# garden_circ.net
KiCad netlist of a schematic drawn in EAGLE
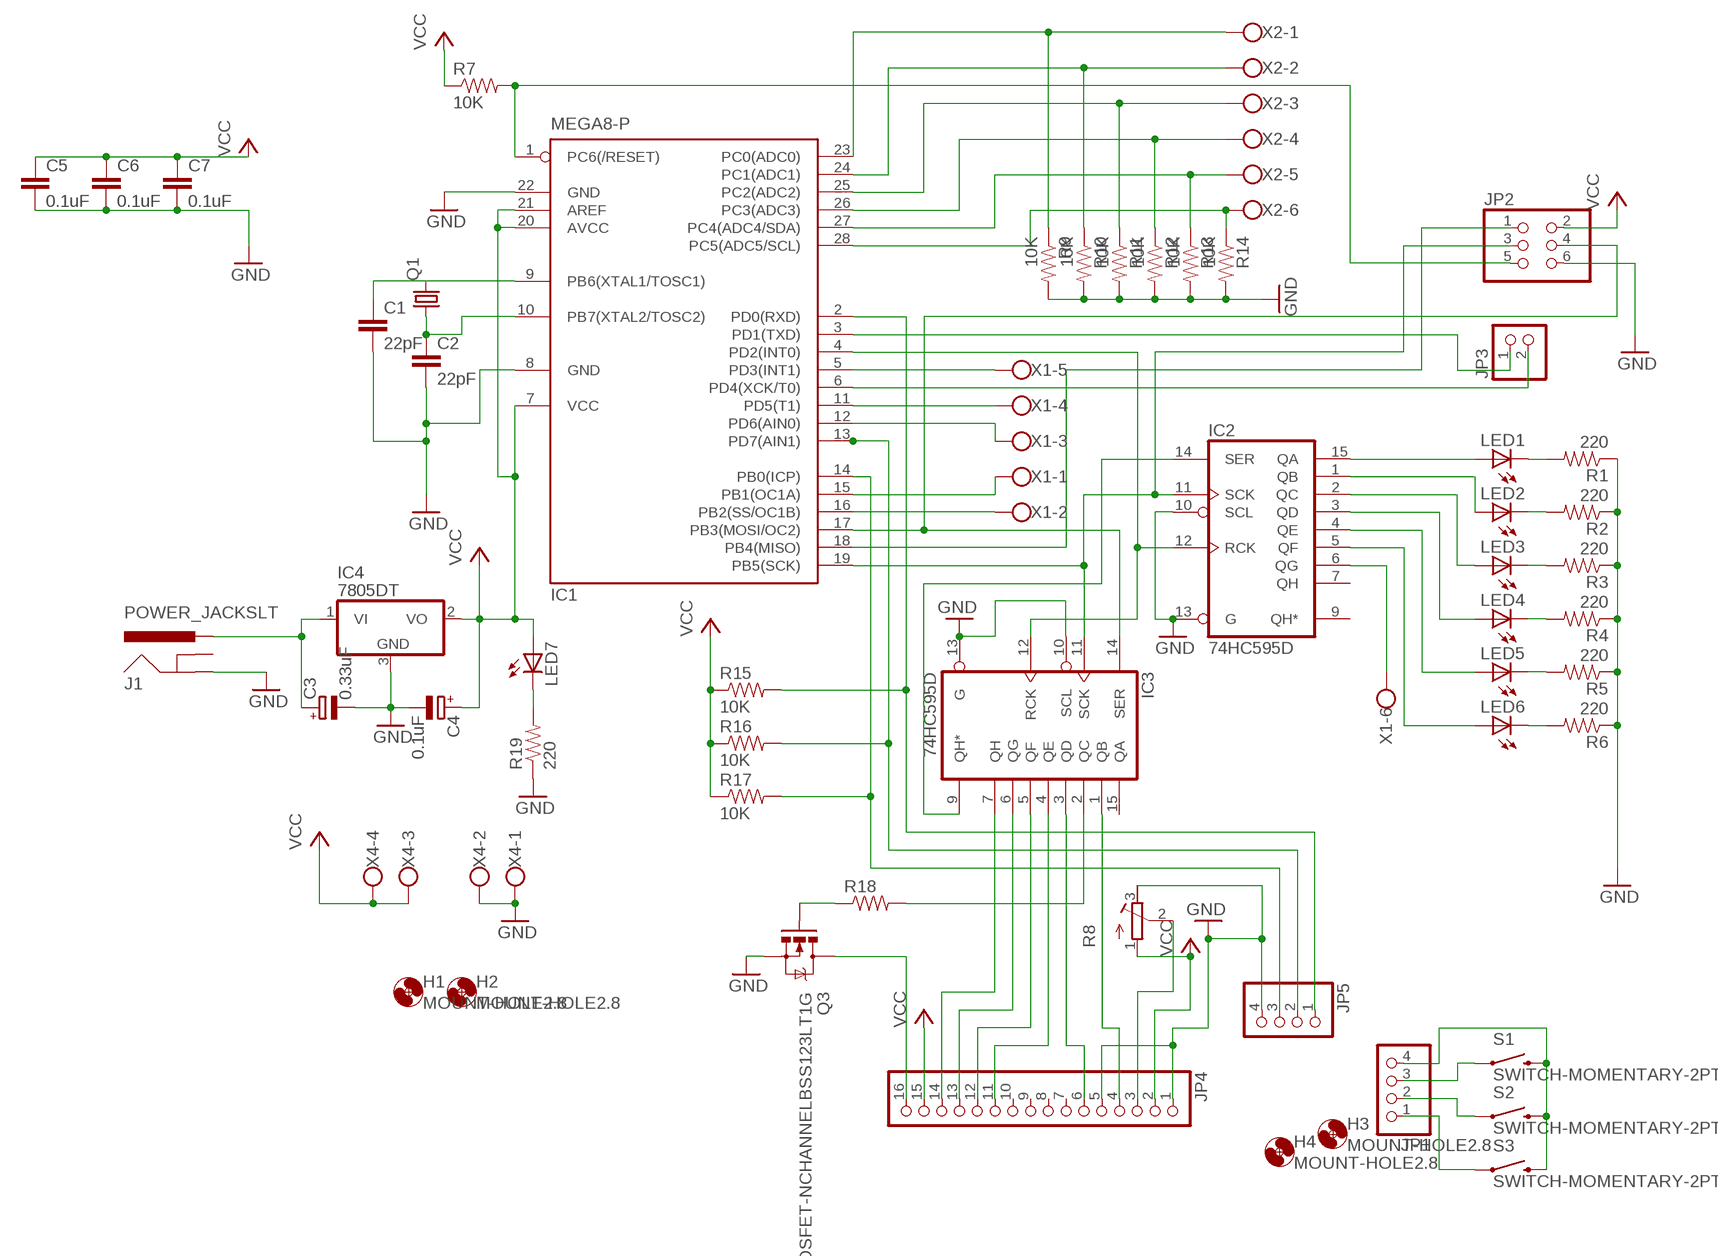
[diagram p0: schematic, sheet 1]

(export (version "E")
  (design (tool "Eeschema 10.0.6"))
  (components
    (comp (ref "C1")
      (value "22pF")
      (footprint "eagle-import:0805")
      (libsource (lib "eagle-import") (part "CAP0805"))
    )
    (comp (ref "C2")
      (value "22pF")
      (footprint "eagle-import:0805")
      (libsource (lib "eagle-import") (part "CAP0805"))
    )
    (comp (ref "C3")
      (value "0.33uF")
      (footprint "eagle-import:SMC_C")
      (libsource (lib "eagle-import") (part "CPOL-EUSMCC"))
    )
    (comp (ref "C4")
      (value "0.1uF")
      (footprint "eagle-import:SMC_C")
      (libsource (lib "eagle-import") (part "CPOL-EUSMCC"))
    )
    (comp (ref "C5")
      (value "0.1uF")
      (footprint "eagle-import:0805")
      (libsource (lib "eagle-import") (part "CAP0805"))
    )
    (comp (ref "C6")
      (value "0.1uF")
      (footprint "eagle-import:0805")
      (libsource (lib "eagle-import") (part "CAP0805"))
    )
    (comp (ref "C7")
      (value "0.1uF")
      (footprint "eagle-import:0805")
      (libsource (lib "eagle-import") (part "CAP0805"))
    )
    (comp (ref "H1")
      (value "MOUNT-HOLE2.8")
      (footprint "eagle-import:2,8")
      (libsource (lib "eagle-import") (part "MOUNT-HOLE2.8"))
    )
    (comp (ref "H2")
      (value "MOUNT-HOLE2.8")
      (footprint "eagle-import:2,8")
      (libsource (lib "eagle-import") (part "MOUNT-HOLE2.8"))
    )
    (comp (ref "H3")
      (value "MOUNT-HOLE2.8")
      (footprint "eagle-import:2,8")
      (libsource (lib "eagle-import") (part "MOUNT-HOLE2.8"))
    )
    (comp (ref "H4")
      (value "MOUNT-HOLE2.8")
      (footprint "eagle-import:2,8")
      (libsource (lib "eagle-import") (part "MOUNT-HOLE2.8"))
    )
    (comp (ref "IC1")
      (value "MEGA8-P")
      (footprint "eagle-import:DIL28-3")
      (libsource (lib "eagle-import") (part "MEGA8-P"))
    )
    (comp (ref "IC2")
      (value "74HC595D")
      (footprint "eagle-import:SO16")
      (libsource (lib "eagle-import") (part "74595DHC"))
    )
    (comp (ref "IC3")
      (value "74HC595D")
      (footprint "eagle-import:SO16")
      (libsource (lib "eagle-import") (part "74595DHC"))
    )
    (comp (ref "IC4")
      (value "7805DT")
      (footprint "eagle-import:TO252")
      (libsource (lib "eagle-import") (part "78DT05"))
    )
    (comp (ref "J1")
      (value "POWER_JACKSLT")
      (footprint "eagle-import:POWER_JACK_SLOT")
      (libsource (lib "eagle-import") (part "POWER_JACKSLT"))
    )
    (comp (ref "JP1")
      (value "PINHD-1X4")
      (footprint "eagle-import:1X04")
      (libsource (lib "eagle-import") (part "PINHD-1X4"))
    )
    (comp (ref "JP2")
      (value "PINHD-2X3")
      (footprint "eagle-import:2X03")
      (libsource (lib "eagle-import") (part "PINHD-2X3"))
    )
    (comp (ref "JP3")
      (value "PINHD-1X2")
      (footprint "eagle-import:1X02")
      (libsource (lib "eagle-import") (part "PINHD-1X2"))
    )
    (comp (ref "JP4")
      (value "PINHD-1X16")
      (footprint "eagle-import:1X16")
      (libsource (lib "eagle-import") (part "PINHD-1X16"))
    )
    (comp (ref "JP5")
      (value "PINHD-1X4")
      (footprint "eagle-import:1X04")
      (libsource (lib "eagle-import") (part "PINHD-1X4"))
    )
    (comp (ref "LED1")
      (value "LED3MM")
      (footprint "eagle-import:LED3MM")
      (libsource (lib "eagle-import") (part "LED3MM"))
    )
    (comp (ref "LED2")
      (value "LED3MM")
      (footprint "eagle-import:LED3MM")
      (libsource (lib "eagle-import") (part "LED3MM"))
    )
    (comp (ref "LED3")
      (value "LED3MM")
      (footprint "eagle-import:LED3MM")
      (libsource (lib "eagle-import") (part "LED3MM"))
    )
    (comp (ref "LED4")
      (value "LED3MM")
      (footprint "eagle-import:LED3MM")
      (libsource (lib "eagle-import") (part "LED3MM"))
    )
    (comp (ref "LED5")
      (value "LED3MM")
      (footprint "eagle-import:LED3MM")
      (libsource (lib "eagle-import") (part "LED3MM"))
    )
    (comp (ref "LED6")
      (value "LED3MM")
      (footprint "eagle-import:LED3MM")
      (libsource (lib "eagle-import") (part "LED3MM"))
    )
    (comp (ref "LED7")
      (value "LEDSML0805")
      (footprint "eagle-import:SML0805")
      (libsource (lib "eagle-import") (part "LEDSML0805"))
    )
    (comp (ref "Q1")
      (value "CRYSTALHC49UP")
      (footprint "eagle-import:HC49UP")
      (libsource (lib "eagle-import") (part "CRYSTALHC49UP"))
    )
    (comp (ref "Q3")
      (value "MOSFET-NCHANNELBSS123LT1G")
      (footprint "eagle-import:SOT23")
      (libsource (lib "eagle-import") (part "MOSFET-NCHANNELBSS123LT1G"))
    )
    (comp (ref "R1")
      (value "220")
      (footprint "eagle-import:0805")
      (libsource (lib "eagle-import") (part "RESISTOR0805-RES"))
    )
    (comp (ref "R2")
      (value "220")
      (footprint "eagle-import:0805")
      (libsource (lib "eagle-import") (part "RESISTOR0805-RES"))
    )
    (comp (ref "R3")
      (value "220")
      (footprint "eagle-import:0805")
      (libsource (lib "eagle-import") (part "RESISTOR0805-RES"))
    )
    (comp (ref "R4")
      (value "220")
      (footprint "eagle-import:0805")
      (libsource (lib "eagle-import") (part "RESISTOR0805-RES"))
    )
    (comp (ref "R5")
      (value "220")
      (footprint "eagle-import:0805")
      (libsource (lib "eagle-import") (part "RESISTOR0805-RES"))
    )
    (comp (ref "R6")
      (value "220")
      (footprint "eagle-import:0805")
      (libsource (lib "eagle-import") (part "RESISTOR0805-RES"))
    )
    (comp (ref "R7")
      (value "10K")
      (footprint "eagle-import:0805")
      (libsource (lib "eagle-import") (part "RESISTOR0805-RES"))
    )
    (comp (ref "R8")
      (value "R-TRIMM3202")
      (footprint "eagle-import:RTRIM3202")
      (libsource (lib "eagle-import") (part "R-TRIMM3202"))
    )
    (comp (ref "R9")
      (value "10K")
      (footprint "eagle-import:0805")
      (libsource (lib "eagle-import") (part "RESISTOR0805-RES"))
    )
    (comp (ref "R10")
      (value "10K")
      (footprint "eagle-import:0805")
      (libsource (lib "eagle-import") (part "RESISTOR0805-RES"))
    )
    (comp (ref "R11")
      (value "10K")
      (footprint "eagle-import:0805")
      (libsource (lib "eagle-import") (part "RESISTOR0805-RES"))
    )
    (comp (ref "R12")
      (value "10K")
      (footprint "eagle-import:0805")
      (libsource (lib "eagle-import") (part "RESISTOR0805-RES"))
    )
    (comp (ref "R13")
      (value "10K")
      (footprint "eagle-import:0805")
      (libsource (lib "eagle-import") (part "RESISTOR0805-RES"))
    )
    (comp (ref "R14")
      (value "10K")
      (footprint "eagle-import:0805")
      (libsource (lib "eagle-import") (part "RESISTOR0805-RES"))
    )
    (comp (ref "R15")
      (value "10K")
      (footprint "eagle-import:0805")
      (libsource (lib "eagle-import") (part "RESISTOR0805-RES"))
    )
    (comp (ref "R16")
      (value "10K")
      (footprint "eagle-import:0805")
      (libsource (lib "eagle-import") (part "RESISTOR0805-RES"))
    )
    (comp (ref "R17")
      (value "10K")
      (footprint "eagle-import:0805")
      (libsource (lib "eagle-import") (part "RESISTOR0805-RES"))
    )
    (comp (ref "R18")
      (value "RESISTOR0805-RES")
      (footprint "eagle-import:0805")
      (libsource (lib "eagle-import") (part "RESISTOR0805-RES"))
    )
    (comp (ref "R19")
      (value "220")
      (footprint "eagle-import:0805")
      (libsource (lib "eagle-import") (part "RESISTOR0805-RES"))
    )
    (comp (ref "S1")
      (value "SWITCH-MOMENTARY-2PTH")
      (footprint "eagle-import:TACTILE-PTH")
      (libsource (lib "eagle-import") (part "SWITCH-MOMENTARY-2PTH"))
    )
    (comp (ref "S2")
      (value "SWITCH-MOMENTARY-2PTH")
      (footprint "eagle-import:TACTILE-PTH")
      (libsource (lib "eagle-import") (part "SWITCH-MOMENTARY-2PTH"))
    )
    (comp (ref "S3")
      (value "SWITCH-MOMENTARY-2PTH")
      (footprint "eagle-import:TACTILE-PTH")
      (libsource (lib "eagle-import") (part "SWITCH-MOMENTARY-2PTH"))
    )
    (comp (ref "X1")
      (value "W237-136")
      (footprint "eagle-import:W237-136")
      (fields (field (name "MPN") "237-136"))
      (libsource (lib "eagle-import") (part "W237-136"))
    )
    (comp (ref "X2")
      (value "W237-136")
      (footprint "eagle-import:W237-136")
      (fields (field (name "MPN") "237-136"))
      (libsource (lib "eagle-import") (part "W237-136"))
    )
    (comp (ref "X4")
      (value "W237-4")
      (footprint "eagle-import:W237-4")
      (libsource (lib "eagle-import") (part "W237-4"))
    )
  )
  (nets
    (net (code "1") (name "GND") (class "Default")
      (node (ref "C1") (pin "2") (pinfunction "2_2") (pintype "passive"))
      (node (ref "C2") (pin "2") (pinfunction "2_2") (pintype "passive"))
      (node (ref "C3") (pin "-") (pinfunction "-_-") (pintype "passive"))
      (node (ref "C4") (pin "-") (pinfunction "-_-") (pintype "passive"))
      (node (ref "C5") (pin "2") (pinfunction "2_2") (pintype "passive"))
      (node (ref "C6") (pin "2") (pinfunction "2_2") (pintype "passive"))
      (node (ref "C7") (pin "2") (pinfunction "2_2") (pintype "passive"))
      (node (ref "IC1") (pin "22") (pinfunction "GND_22") (pintype "power_in"))
      (node (ref "IC1") (pin "8") (pinfunction "GND_8") (pintype "power_in"))
      (node (ref "IC2") (pin "10") (pinfunction "SCL_10") (pintype "input"))
      (node (ref "IC2") (pin "13") (pinfunction "G_13") (pintype "input"))
      (node (ref "IC3") (pin "10") (pinfunction "SCL_10") (pintype "input"))
      (node (ref "IC3") (pin "13") (pinfunction "G_13") (pintype "input"))
      (node (ref "IC4") (pin "3") (pinfunction "GND_3") (pintype "passive"))
      (node (ref "J1") (pin "GND@2") (pinfunction "GND_GND@2") (pintype "bidirectional"))
      (node (ref "JP2") (pin "6") (pinfunction "6_6") (pintype "passive"))
      (node (ref "JP4") (pin "1") (pinfunction "1_1") (pintype "passive"))
      (node (ref "JP4") (pin "5") (pinfunction "5_5") (pintype "passive"))
      (node (ref "JP5") (pin "4") (pinfunction "4_4") (pintype "passive"))
      (node (ref "Q3") (pin "2") (pinfunction "S_2") (pintype "passive"))
      (node (ref "R1") (pin "1") (pinfunction "1_1") (pintype "passive"))
      (node (ref "R10") (pin "2") (pinfunction "2_2") (pintype "passive"))
      (node (ref "R11") (pin "2") (pinfunction "2_2") (pintype "passive"))
      (node (ref "R12") (pin "2") (pinfunction "2_2") (pintype "passive"))
      (node (ref "R13") (pin "2") (pinfunction "2_2") (pintype "passive"))
      (node (ref "R14") (pin "2") (pinfunction "2_2") (pintype "passive"))
      (node (ref "R19") (pin "1") (pinfunction "1_1") (pintype "passive"))
      (node (ref "R2") (pin "1") (pinfunction "1_1") (pintype "passive"))
      (node (ref "R3") (pin "1") (pinfunction "1_1") (pintype "passive"))
      (node (ref "R4") (pin "1") (pinfunction "1_1") (pintype "passive"))
      (node (ref "R5") (pin "1") (pinfunction "1_1") (pintype "passive"))
      (node (ref "R6") (pin "1") (pinfunction "1_1") (pintype "passive"))
      (node (ref "R8") (pin "3") (pinfunction "A_3") (pintype "passive"))
      (node (ref "R9") (pin "2") (pinfunction "2_2") (pintype "passive"))
      (node (ref "X4") (pin "1") (pinfunction "KL_1") (pintype "passive"))
      (node (ref "X4") (pin "2") (pinfunction "KL_2") (pintype "passive"))
    )
    (net (code "2") (name "Net-(IC1-PB0(ICP))") (class "Default")
      (node (ref "IC1") (pin "14") (pinfunction "PB0(ICP)_14") (pintype "bidirectional"))
      (node (ref "JP5") (pin "3") (pinfunction "3_3") (pintype "passive"))
      (node (ref "R17") (pin "2") (pinfunction "2_2") (pintype "passive"))
    )
    (net (code "3") (name "Net-(IC1-PB1(OC1A))") (class "Default")
      (node (ref "IC1") (pin "15") (pinfunction "PB1(OC1A)_15") (pintype "bidirectional"))
      (node (ref "X1") (pin "1") (pinfunction "KL_1") (pintype "passive"))
    )
    (net (code "4") (name "Net-(IC1-PB2(SS{slash}OC1B))") (class "Default")
      (node (ref "IC1") (pin "16") (pinfunction "PB2(SS/OC1B)_16") (pintype "bidirectional"))
      (node (ref "X1") (pin "2") (pinfunction "KL_2") (pintype "passive"))
    )
    (net (code "5") (name "Net-(IC1-PB3(MOSI{slash}OC2))") (class "Default")
      (node (ref "IC1") (pin "17") (pinfunction "PB3(MOSI/OC2)_17") (pintype "bidirectional"))
      (node (ref "IC3") (pin "14") (pinfunction "SER_14") (pintype "input"))
      (node (ref "JP2") (pin "4") (pinfunction "4_4") (pintype "passive"))
    )
    (net (code "6") (name "Net-(IC1-PB4(MISO))") (class "Default")
      (node (ref "IC1") (pin "18") (pinfunction "PB4(MISO)_18") (pintype "bidirectional"))
      (node (ref "JP2") (pin "1") (pinfunction "1_1") (pintype "passive"))
    )
    (net (code "7") (name "Net-(IC1-PB5(SCK))") (class "Default")
      (node (ref "IC1") (pin "19") (pinfunction "PB5(SCK)_19") (pintype "bidirectional"))
      (node (ref "IC2") (pin "11") (pinfunction "SCK_11") (pintype "input"))
      (node (ref "IC3") (pin "11") (pinfunction "SCK_11") (pintype "input"))
      (node (ref "JP2") (pin "3") (pinfunction "3_3") (pintype "passive"))
    )
    (net (code "8") (name "Net-(IC1-PB6(XTAL1{slash}TOSC1))") (class "Default")
      (node (ref "C1") (pin "1") (pinfunction "1_1") (pintype "passive"))
      (node (ref "IC1") (pin "9") (pinfunction "PB6(XTAL1/TOSC1)_9") (pintype "bidirectional"))
      (node (ref "Q1") (pin "2") (pinfunction "2_2") (pintype "passive"))
    )
    (net (code "9") (name "Net-(IC1-PB7(XTAL2{slash}TOSC2))") (class "Default")
      (node (ref "C2") (pin "1") (pinfunction "1_1") (pintype "passive"))
      (node (ref "IC1") (pin "10") (pinfunction "PB7(XTAL2/TOSC2)_10") (pintype "bidirectional"))
      (node (ref "Q1") (pin "1") (pinfunction "1_1") (pintype "passive"))
    )
    (net (code "10") (name "Net-(IC1-PC0(ADC0))") (class "Default")
      (node (ref "IC1") (pin "23") (pinfunction "PC0(ADC0)_23") (pintype "bidirectional"))
      (node (ref "R9") (pin "1") (pinfunction "1_1") (pintype "passive"))
      (node (ref "X2") (pin "1") (pinfunction "KL_1") (pintype "passive"))
    )
    (net (code "11") (name "Net-(IC1-PC1(ADC1))") (class "Default")
      (node (ref "IC1") (pin "24") (pinfunction "PC1(ADC1)_24") (pintype "bidirectional"))
      (node (ref "R10") (pin "1") (pinfunction "1_1") (pintype "passive"))
      (node (ref "X2") (pin "2") (pinfunction "KL_2") (pintype "passive"))
    )
    (net (code "12") (name "Net-(IC1-PC2(ADC2))") (class "Default")
      (node (ref "IC1") (pin "25") (pinfunction "PC2(ADC2)_25") (pintype "bidirectional"))
      (node (ref "R11") (pin "1") (pinfunction "1_1") (pintype "passive"))
      (node (ref "X2") (pin "3") (pinfunction "KL_3") (pintype "passive"))
    )
    (net (code "13") (name "Net-(IC1-PC3(ADC3))") (class "Default")
      (node (ref "IC1") (pin "26") (pinfunction "PC3(ADC3)_26") (pintype "bidirectional"))
      (node (ref "R12") (pin "1") (pinfunction "1_1") (pintype "passive"))
      (node (ref "X2") (pin "4") (pinfunction "KL_4") (pintype "passive"))
    )
    (net (code "14") (name "Net-(IC1-PC4(ADC4{slash}SDA))") (class "Default")
      (node (ref "IC1") (pin "27") (pinfunction "PC4(ADC4/SDA)_27") (pintype "bidirectional"))
      (node (ref "R13") (pin "1") (pinfunction "1_1") (pintype "passive"))
      (node (ref "X2") (pin "5") (pinfunction "KL_5") (pintype "passive"))
    )
    (net (code "15") (name "Net-(IC1-PC5(ADC5{slash}SCL))") (class "Default")
      (node (ref "IC1") (pin "28") (pinfunction "PC5(ADC5/SCL)_28") (pintype "bidirectional"))
      (node (ref "R14") (pin "1") (pinfunction "1_1") (pintype "passive"))
      (node (ref "X2") (pin "6") (pinfunction "KL_6") (pintype "passive"))
    )
    (net (code "16") (name "Net-(IC1-PC6({slash}RESET))") (class "Default")
      (node (ref "IC1") (pin "1") (pinfunction "PC6(/RESET)_1") (pintype "bidirectional"))
      (node (ref "JP2") (pin "5") (pinfunction "5_5") (pintype "passive"))
      (node (ref "R7") (pin "2") (pinfunction "2_2") (pintype "passive"))
    )
    (net (code "17") (name "Net-(IC1-PD0(RXD))") (class "Default")
      (node (ref "IC1") (pin "2") (pinfunction "PD0(RXD)_2") (pintype "bidirectional"))
      (node (ref "JP5") (pin "1") (pinfunction "1_1") (pintype "passive"))
      (node (ref "R15") (pin "2") (pinfunction "2_2") (pintype "passive"))
    )
    (net (code "18") (name "Net-(IC1-PD1(TXD))") (class "Default")
      (node (ref "IC1") (pin "3") (pinfunction "PD1(TXD)_3") (pintype "bidirectional"))
      (node (ref "JP3") (pin "1") (pinfunction "1_1") (pintype "passive"))
    )
    (net (code "19") (name "Net-(IC1-PD2(INT0))") (class "Default")
      (node (ref "IC1") (pin "4") (pinfunction "PD2(INT0)_4") (pintype "bidirectional"))
      (node (ref "IC2") (pin "12") (pinfunction "RCK_12") (pintype "input"))
      (node (ref "IC3") (pin "12") (pinfunction "RCK_12") (pintype "input"))
    )
    (net (code "20") (name "Net-(IC1-PD3(INT1))") (class "Default")
      (node (ref "IC1") (pin "5") (pinfunction "PD3(INT1)_5") (pintype "bidirectional"))
      (node (ref "X1") (pin "5") (pinfunction "KL_5") (pintype "passive"))
    )
    (net (code "21") (name "Net-(IC1-PD4(XCK{slash}T0))") (class "Default")
      (node (ref "IC1") (pin "6") (pinfunction "PD4(XCK/T0)_6") (pintype "bidirectional"))
      (node (ref "JP3") (pin "2") (pinfunction "2_2") (pintype "passive"))
    )
    (net (code "22") (name "Net-(IC1-PD5(T1))") (class "Default")
      (node (ref "IC1") (pin "11") (pinfunction "PD5(T1)_11") (pintype "bidirectional"))
      (node (ref "X1") (pin "4") (pinfunction "KL_4") (pintype "passive"))
    )
    (net (code "23") (name "Net-(IC1-PD6(AIN0))") (class "Default")
      (node (ref "IC1") (pin "12") (pinfunction "PD6(AIN0)_12") (pintype "bidirectional"))
      (node (ref "X1") (pin "3") (pinfunction "KL_3") (pintype "passive"))
    )
    (net (code "24") (name "Net-(IC1-PD7(AIN1))") (class "Default")
      (node (ref "IC1") (pin "13") (pinfunction "PD7(AIN1)_13") (pintype "bidirectional"))
      (node (ref "JP5") (pin "2") (pinfunction "2_2") (pintype "passive"))
      (node (ref "R16") (pin "2") (pinfunction "2_2") (pintype "passive"))
    )
    (net (code "25") (name "Net-(IC2A-QA)") (class "Default")
      (node (ref "IC2") (pin "15") (pinfunction "QA_15") (pintype "tri_state"))
      (node (ref "LED1") (pin "A") (pinfunction "A_A") (pintype "passive"))
    )
    (net (code "26") (name "Net-(IC2A-QB)") (class "Default")
      (node (ref "IC2") (pin "1") (pinfunction "QB_1") (pintype "tri_state"))
      (node (ref "LED2") (pin "A") (pinfunction "A_A") (pintype "passive"))
    )
    (net (code "27") (name "Net-(IC2A-QC)") (class "Default")
      (node (ref "IC2") (pin "2") (pinfunction "QC_2") (pintype "tri_state"))
      (node (ref "LED3") (pin "A") (pinfunction "A_A") (pintype "passive"))
    )
    (net (code "28") (name "Net-(IC2A-QD)") (class "Default")
      (node (ref "IC2") (pin "3") (pinfunction "QD_3") (pintype "tri_state"))
      (node (ref "LED4") (pin "A") (pinfunction "A_A") (pintype "passive"))
    )
    (net (code "29") (name "Net-(IC2A-QE)") (class "Default")
      (node (ref "IC2") (pin "4") (pinfunction "QE_4") (pintype "tri_state"))
      (node (ref "LED5") (pin "A") (pinfunction "A_A") (pintype "passive"))
    )
    (net (code "30") (name "Net-(IC2A-QF)") (class "Default")
      (node (ref "IC2") (pin "5") (pinfunction "QF_5") (pintype "tri_state"))
      (node (ref "LED6") (pin "A") (pinfunction "A_A") (pintype "passive"))
    )
    (net (code "31") (name "Net-(IC2A-QG)") (class "Default")
      (node (ref "IC2") (pin "6") (pinfunction "QG_6") (pintype "tri_state"))
      (node (ref "X1") (pin "6") (pinfunction "KL_6") (pintype "passive"))
    )
    (net (code "32") (name "Net-(IC2A-SER)") (class "Default")
      (node (ref "IC2") (pin "14") (pinfunction "SER_14") (pintype "input"))
      (node (ref "IC3") (pin "9") (pinfunction "QH*_9") (pintype "tri_state"))
    )
    (net (code "33") (name "Net-(IC3A-QB)") (class "Default")
      (node (ref "IC3") (pin "1") (pinfunction "QB_1") (pintype "tri_state"))
      (node (ref "JP4") (pin "4") (pinfunction "4_4") (pintype "passive"))
    )
    (net (code "34") (name "Net-(IC3A-QC)") (class "Default")
      (node (ref "IC3") (pin "2") (pinfunction "QC_2") (pintype "tri_state"))
      (node (ref "R18") (pin "2") (pinfunction "2_2") (pintype "passive"))
    )
    (net (code "35") (name "Net-(IC3A-QD)") (class "Default")
      (node (ref "IC3") (pin "3") (pinfunction "QD_3") (pintype "tri_state"))
      (node (ref "JP4") (pin "6") (pinfunction "6_6") (pintype "passive"))
    )
    (net (code "36") (name "Net-(IC3A-QE)") (class "Default")
      (node (ref "IC3") (pin "4") (pinfunction "QE_4") (pintype "tri_state"))
      (node (ref "JP4") (pin "11") (pinfunction "11_11") (pintype "passive"))
    )
    (net (code "37") (name "Net-(IC3A-QF)") (class "Default")
      (node (ref "IC3") (pin "5") (pinfunction "QF_5") (pintype "tri_state"))
      (node (ref "JP4") (pin "12") (pinfunction "12_12") (pintype "passive"))
    )
    (net (code "38") (name "Net-(IC3A-QG)") (class "Default")
      (node (ref "IC3") (pin "6") (pinfunction "QG_6") (pintype "tri_state"))
      (node (ref "JP4") (pin "13") (pinfunction "13_13") (pintype "passive"))
    )
    (net (code "39") (name "Net-(IC3A-QH)") (class "Default")
      (node (ref "IC3") (pin "7") (pinfunction "QH_7") (pintype "tri_state"))
      (node (ref "JP4") (pin "14") (pinfunction "14_14") (pintype "passive"))
    )
    (net (code "40") (name "Net-(IC4-VI)") (class "Default")
      (node (ref "C3") (pin "+") (pinfunction "+_+") (pintype "passive"))
      (node (ref "IC4") (pin "1") (pinfunction "VI_1") (pintype "input"))
      (node (ref "J1") (pin "PWR") (pinfunction "PWR_PWR") (pintype "bidirectional"))
    )
    (net (code "41") (name "Net-(JP1-Pad1)") (class "Default")
      (node (ref "JP1") (pin "1") (pinfunction "1_1") (pintype "passive"))
      (node (ref "S3") (pin "1") (pinfunction "1_1") (pintype "passive"))
    )
    (net (code "42") (name "Net-(JP1-Pad2)") (class "Default")
      (node (ref "JP1") (pin "2") (pinfunction "2_2") (pintype "passive"))
      (node (ref "S2") (pin "1") (pinfunction "1_1") (pintype "passive"))
    )
    (net (code "43") (name "Net-(JP1-Pad3)") (class "Default")
      (node (ref "JP1") (pin "3") (pinfunction "3_3") (pintype "passive"))
      (node (ref "S1") (pin "1") (pinfunction "1_1") (pintype "passive"))
    )
    (net (code "44") (name "Net-(LED1-C)") (class "Default")
      (node (ref "LED1") (pin "K") (pinfunction "C_K") (pintype "passive"))
      (node (ref "R1") (pin "2") (pinfunction "2_2") (pintype "passive"))
    )
    (net (code "45") (name "Net-(LED2-C)") (class "Default")
      (node (ref "LED2") (pin "K") (pinfunction "C_K") (pintype "passive"))
      (node (ref "R2") (pin "2") (pinfunction "2_2") (pintype "passive"))
    )
    (net (code "46") (name "Net-(LED3-C)") (class "Default")
      (node (ref "LED3") (pin "K") (pinfunction "C_K") (pintype "passive"))
      (node (ref "R3") (pin "2") (pinfunction "2_2") (pintype "passive"))
    )
    (net (code "47") (name "Net-(LED4-C)") (class "Default")
      (node (ref "LED4") (pin "K") (pinfunction "C_K") (pintype "passive"))
      (node (ref "R4") (pin "2") (pinfunction "2_2") (pintype "passive"))
    )
    (net (code "48") (name "Net-(LED5-C)") (class "Default")
      (node (ref "LED5") (pin "K") (pinfunction "C_K") (pintype "passive"))
      (node (ref "R5") (pin "2") (pinfunction "2_2") (pintype "passive"))
    )
    (net (code "49") (name "Net-(LED6-C)") (class "Default")
      (node (ref "LED6") (pin "K") (pinfunction "C_K") (pintype "passive"))
      (node (ref "R6") (pin "2") (pinfunction "2_2") (pintype "passive"))
    )
    (net (code "50") (name "Net-(LED7-PadC)") (class "Default")
      (node (ref "LED7") (pin "C") (pinfunction "C_C") (pintype "passive"))
      (node (ref "R19") (pin "2") (pinfunction "2_2") (pintype "passive"))
    )
    (net (code "51") (name "Net-(Q3-D)") (class "Default")
      (node (ref "JP4") (pin "16") (pinfunction "16_16") (pintype "passive"))
      (node (ref "Q3") (pin "3") (pinfunction "D_3") (pintype "passive"))
    )
    (net (code "52") (name "Net-(Q3-G)") (class "Default")
      (node (ref "Q3") (pin "1") (pinfunction "G_1") (pintype "passive"))
      (node (ref "R18") (pin "1") (pinfunction "1_1") (pintype "passive"))
    )
    (net (code "53") (name "Net-(R8-S)") (class "Default")
      (node (ref "JP4") (pin "3") (pinfunction "3_3") (pintype "passive"))
      (node (ref "R8") (pin "2") (pinfunction "S_2") (pintype "passive"))
    )
    (net (code "54") (name "Net-(S1-2)") (class "Default")
      (node (ref "JP1") (pin "4") (pinfunction "4_4") (pintype "passive"))
      (node (ref "S1") (pin "3") (pinfunction "2_3") (pintype "passive"))
      (node (ref "S2") (pin "3") (pinfunction "2_3") (pintype "passive"))
      (node (ref "S3") (pin "3") (pinfunction "2_3") (pintype "passive"))
    )
    (net (code "55") (name "VCC") (class "Default")
      (node (ref "C4") (pin "+") (pinfunction "+_+") (pintype "passive"))
      (node (ref "C5") (pin "1") (pinfunction "1_1") (pintype "passive"))
      (node (ref "C6") (pin "1") (pinfunction "1_1") (pintype "passive"))
      (node (ref "C7") (pin "1") (pinfunction "1_1") (pintype "passive"))
      (node (ref "IC1") (pin "20") (pinfunction "AVCC_20") (pintype "power_in"))
      (node (ref "IC1") (pin "21") (pinfunction "AREF_21") (pintype "passive"))
      (node (ref "IC1") (pin "7") (pinfunction "VCC_7") (pintype "power_in"))
      (node (ref "IC4") (pin "2") (pinfunction "VO_2") (pintype "passive"))
      (node (ref "JP2") (pin "2") (pinfunction "2_2") (pintype "passive"))
      (node (ref "JP4") (pin "15") (pinfunction "15_15") (pintype "passive"))
      (node (ref "JP4") (pin "2") (pinfunction "2_2") (pintype "passive"))
      (node (ref "LED7") (pin "A") (pinfunction "A_A") (pintype "passive"))
      (node (ref "R15") (pin "1") (pinfunction "1_1") (pintype "passive"))
      (node (ref "R16") (pin "1") (pinfunction "1_1") (pintype "passive"))
      (node (ref "R17") (pin "1") (pinfunction "1_1") (pintype "passive"))
      (node (ref "R7") (pin "1") (pinfunction "1_1") (pintype "passive"))
      (node (ref "R8") (pin "1") (pinfunction "E_1") (pintype "passive"))
      (node (ref "X4") (pin "3") (pinfunction "KL_3") (pintype "passive"))
      (node (ref "X4") (pin "4") (pinfunction "KL_4") (pintype "passive"))
    )
    (net (code "56") (name "unconnected-(IC2A-QH*-Pad9)") (class "Default")
      (node (ref "IC2") (pin "9") (pinfunction "QH*_9") (pintype "tri_state"))
    )
    (net (code "57") (name "unconnected-(IC2A-QH-Pad7)") (class "Default")
      (node (ref "IC2") (pin "7") (pinfunction "QH_7") (pintype "tri_state"))
    )
    (net (code "58") (name "unconnected-(IC3A-QA-Pad15)") (class "Default")
      (node (ref "IC3") (pin "15") (pinfunction "QA_15") (pintype "tri_state"))
    )
    (net (code "59") (name "unconnected-(J1-GNDBREAK-PadGND@1)") (class "Default")
      (node (ref "J1") (pin "GND@1") (pinfunction "GNDBREAK_GND@1") (pintype "bidirectional"))
    )
    (net (code "60") (name "unconnected-(JP4-Pad7)") (class "Default")
      (node (ref "JP4") (pin "7") (pinfunction "7_7") (pintype "passive"))
    )
    (net (code "61") (name "unconnected-(JP4-Pad8)") (class "Default")
      (node (ref "JP4") (pin "8") (pinfunction "8_8") (pintype "passive"))
    )
    (net (code "62") (name "unconnected-(JP4-Pad9)") (class "Default")
      (node (ref "JP4") (pin "9") (pinfunction "9_9") (pintype "passive"))
    )
    (net (code "63") (name "unconnected-(JP4-Pad10)") (class "Default")
      (node (ref "JP4") (pin "10") (pinfunction "10_10") (pintype "passive"))
    )
  )
)
